# boot.net
KiCad netlist of a schematic drawn in Altium Designer
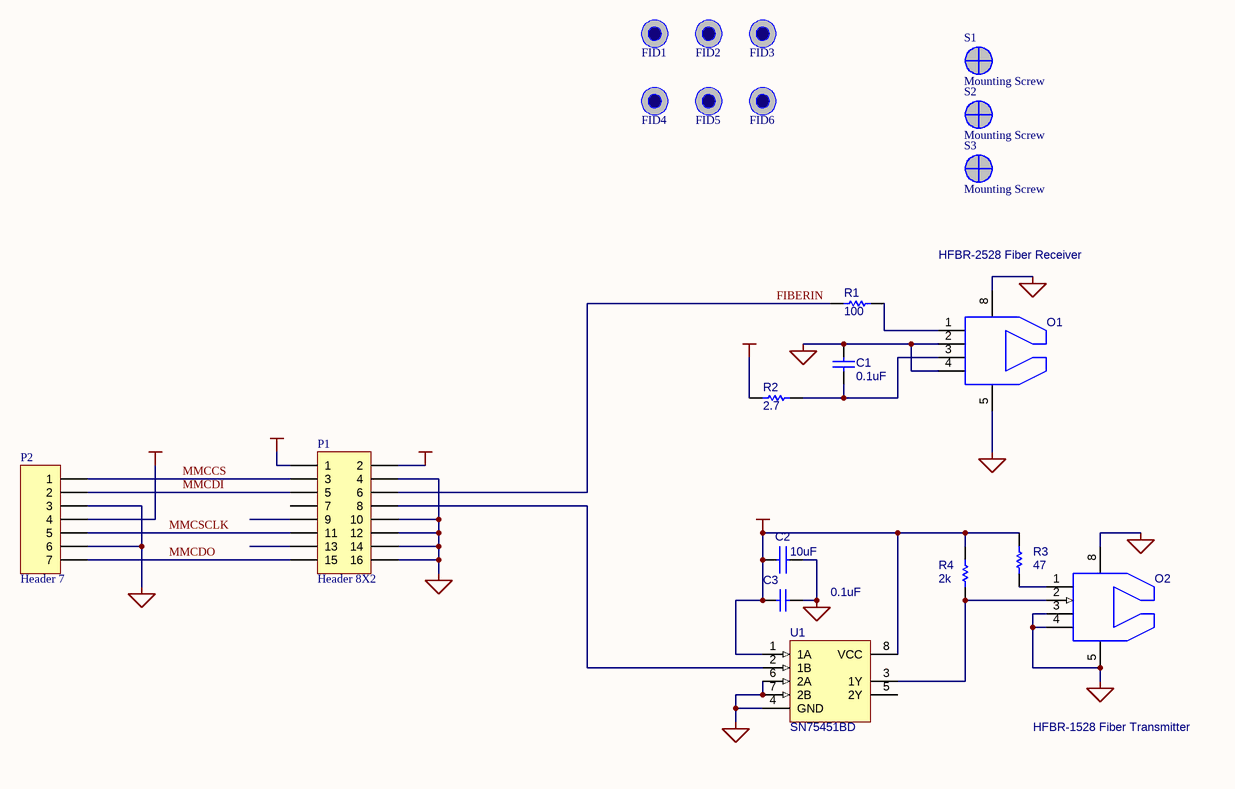
[diagram p0: boot.SCHDOC]

(export (version "E")
  (design (tool "Eeschema 10.0.6"))
  (components
    (comp (ref "C1")
      (value "0.1uF")
      (footprint "CC1608-0603")
      (description "Capacitor")
      (fields
        (field (name "MANUFACTURER") "Generic Components")
        (field (name "Comment") "Cap")
        (field (name "PUBLISHER") "Altium Limited")
      )
      (libsource (lib "Miscellaneous Devices") (part "Cap"))
    )
    (comp (ref "C2")
      (value "10uF")
      (footprint "0603")
      (description "Standard Capacitor")
      (fields (field (name "Comment") "CAPACITOR"))
      (libsource (lib "parts") (part "CAPACITOR"))
    )
    (comp (ref "C3")
      (value "0.1uF")
      (footprint "CC1608-0603")
      (description "Capacitor")
      (fields
        (field (name "MANUFACTURER") "Generic Components")
        (field (name "Comment") "Cap")
        (field (name "PUBLISHER") "Altium Limited")
      )
      (libsource (lib "Miscellaneous Devices") (part "Cap"))
    )
    (comp (ref "FID1")
      (value "FIDUCIAL")
      (footprint "FIDUCIAL")
      (description "Fiducial")
      (libsource (lib "parts") (part "FIDUCIAL"))
    )
    (comp (ref "FID2")
      (value "FIDUCIAL")
      (footprint "FIDUCIAL")
      (description "Fiducial")
      (libsource (lib "parts") (part "FIDUCIAL"))
    )
    (comp (ref "FID3")
      (value "FIDUCIAL")
      (footprint "FIDUCIAL")
      (description "Fiducial")
      (libsource (lib "parts") (part "FIDUCIAL"))
    )
    (comp (ref "FID4")
      (value "FIDUCIAL")
      (footprint "FIDUCIAL")
      (description "Fiducial")
      (libsource (lib "parts") (part "FIDUCIAL"))
    )
    (comp (ref "FID5")
      (value "FIDUCIAL")
      (footprint "FIDUCIAL")
      (description "Fiducial")
      (libsource (lib "parts") (part "FIDUCIAL"))
    )
    (comp (ref "FID6")
      (value "FIDUCIAL")
      (footprint "FIDUCIAL")
      (description "Fiducial")
      (libsource (lib "parts") (part "FIDUCIAL"))
    )
    (comp (ref "O1")
      (value "HFBR-2528 Fiber Receiver")
      (footprint "HPVL")
      (description "Low-cost fiber receiver")
      (libsource (lib "parts") (part "HFBR-2528"))
    )
    (comp (ref "O2")
      (value "HFBR-1528 Fiber Transmitter")
      (footprint "HPVL")
      (description "Low-cost fiber transmitter")
      (libsource (lib "parts") (part "HFBR-1528"))
    )
    (comp (ref "P1")
      (value "Header 8X2")
      (footprint "MOLEX 15-91-2160")
      (description "Header, 8-Pin, Dual row")
      (fields (field (name "PUBLISHER") "Altium Limited"))
      (libsource (lib "Miscellaneous Connectors") (part "Header 8X2"))
    )
    (comp (ref "P2")
      (value "Header 7")
      (footprint "SCDA1A1501")
      (description "Header, 7-Pin")
      (fields (field (name "PUBLISHER") "Altium Limited"))
      (libsource (lib "Miscellaneous Connectors") (part "Header 7"))
    )
    (comp (ref "R1")
      (value "100")
      (footprint "CR1608-0603")
      (description "Resistor")
      (fields
        (field (name "MANUFACTURER") "Generic Components")
        (field (name "Comment") "Res1")
        (field (name "PUBLISHER") "Altium Limited")
      )
      (libsource (lib "Miscellaneous Devices") (part "Res1"))
    )
    (comp (ref "R2")
      (value "2.7")
      (footprint "CR1608-0603")
      (description "Resistor")
      (fields
        (field (name "MANUFACTURER") "Generic Components")
        (field (name "Comment") "Res1")
        (field (name "PUBLISHER") "Altium Limited")
      )
      (libsource (lib "Miscellaneous Devices") (part "Res1"))
    )
    (comp (ref "R3")
      (value "47")
      (footprint "CR1608-0603")
      (description "Resistor")
      (fields
        (field (name "MANUFACTURER") "Generic Components")
        (field (name "Comment") "Res1")
        (field (name "PUBLISHER") "Altium Limited")
      )
      (libsource (lib "Miscellaneous Devices") (part "Res1"))
    )
    (comp (ref "R4")
      (value "2k")
      (footprint "CR1608-0603")
      (description "Resistor")
      (fields
        (field (name "MANUFACTURER") "Generic Components")
        (field (name "Comment") "Res1")
        (field (name "PUBLISHER") "Altium Limited")
      )
      (libsource (lib "Miscellaneous Devices") (part "Res1"))
    )
    (comp (ref "S1")
      (value "Mounting Screw")
      (footprint "SCREW6-32")
      (libsource (lib "parts") (part "MNTSCREW"))
    )
    (comp (ref "S2")
      (value "Mounting Screw")
      (footprint "SCREW6-32")
      (libsource (lib "parts") (part "MNTSCREW"))
    )
    (comp (ref "S3")
      (value "Mounting Screw")
      (footprint "SCREW6-32")
      (libsource (lib "parts") (part "MNTSCREW"))
    )
    (comp (ref "U1")
      (value "SN75451BD")
      (footprint "SO-G8/E2.5")
      (description "Dual Peripheral Driver")
      (fields (field (name "MANUFACTURER") "Texas Instruments") (field (name "PUBLISHER") "Altium Limited"))
      (libsource (lib "TI Interface Peripheral Driver") (part "SN75451BD"))
    )
  )
  (nets
    (net (code "1") (name "+5VCC") (class "Default")
      (node (ref "C2") (pin "1") (pintype "passive"))
      (node (ref "C3") (pin "1") (pinfunction "1_1") (pintype "passive"))
      (node (ref "P1") (pin "2") (pinfunction "2_2") (pintype "passive"))
      (node (ref "R2") (pin "1") (pinfunction "1_1") (pintype "passive"))
      (node (ref "R3") (pin "2") (pinfunction "2_2") (pintype "passive"))
      (node (ref "R4") (pin "2") (pinfunction "2_2") (pintype "passive"))
      (node (ref "U1") (pin "1") (pinfunction "1A_1") (pintype "input"))
      (node (ref "U1") (pin "8") (pinfunction "VCC_8") (pintype "power_in"))
    )
    (net (code "2") (name "/FIBERIN") (class "Default")
      (node (ref "P1") (pin "6") (pinfunction "6_6") (pintype "passive"))
      (node (ref "R1") (pin "1") (pinfunction "1_1") (pintype "passive"))
    )
    (net (code "3") (name "/MMCCS") (class "Default")
      (node (ref "P1") (pin "3") (pinfunction "3_3") (pintype "passive"))
      (node (ref "P2") (pin "1") (pinfunction "1_1") (pintype "passive"))
    )
    (net (code "4") (name "/MMCDI") (class "Default")
      (node (ref "P1") (pin "5") (pinfunction "5_5") (pintype "passive"))
      (node (ref "P2") (pin "2") (pinfunction "2_2") (pintype "passive"))
    )
    (net (code "5") (name "/MMCDO") (class "Default")
      (node (ref "P1") (pin "15") (pinfunction "15_15") (pintype "passive"))
      (node (ref "P2") (pin "7") (pinfunction "7_7") (pintype "passive"))
    )
    (net (code "6") (name "/MMCSCLK") (class "Default")
      (node (ref "P1") (pin "11") (pinfunction "11_11") (pintype "passive"))
      (node (ref "P2") (pin "5") (pinfunction "5_5") (pintype "passive"))
    )
    (net (code "7") (name "GND") (class "Default")
      (node (ref "C1") (pin "2") (pinfunction "2_2") (pintype "passive"))
      (node (ref "C2") (pin "2") (pintype "passive"))
      (node (ref "C3") (pin "2") (pinfunction "2_2") (pintype "passive"))
      (node (ref "O1") (pin "2") (pintype "power_in"))
      (node (ref "O1") (pin "4") (pintype "power_in"))
      (node (ref "O1") (pin "5") (pintype "power_in"))
      (node (ref "O1") (pin "8") (pintype "power_in"))
      (node (ref "O2") (pin "3") (pintype "power_in"))
      (node (ref "O2") (pin "4") (pintype "power_in"))
      (node (ref "O2") (pin "5") (pintype "power_in"))
      (node (ref "O2") (pin "8") (pintype "power_in"))
      (node (ref "P1") (pin "10") (pinfunction "10_10") (pintype "passive"))
      (node (ref "P1") (pin "12") (pinfunction "12_12") (pintype "passive"))
      (node (ref "P1") (pin "14") (pinfunction "14_14") (pintype "passive"))
      (node (ref "P1") (pin "16") (pinfunction "16_16") (pintype "passive"))
      (node (ref "P1") (pin "4") (pinfunction "4_4") (pintype "passive"))
      (node (ref "P2") (pin "3") (pinfunction "3_3") (pintype "passive"))
      (node (ref "P2") (pin "6") (pinfunction "6_6") (pintype "passive"))
      (node (ref "U1") (pin "4") (pinfunction "GND_4") (pintype "power_in"))
      (node (ref "U1") (pin "6") (pinfunction "2A_6") (pintype "input"))
      (node (ref "U1") (pin "7") (pinfunction "2B_7") (pintype "input"))
    )
    (net (code "8") (name "Net-(C1-Pad1)") (class "Default")
      (node (ref "C1") (pin "1") (pinfunction "1_1") (pintype "passive"))
      (node (ref "O1") (pin "3") (pintype "power_in"))
      (node (ref "R2") (pin "2") (pinfunction "2_2") (pintype "passive"))
    )
    (net (code "9") (name "Net-(O1-Pad1)") (class "Default")
      (node (ref "O1") (pin "1") (pintype "power_in"))
      (node (ref "R1") (pin "2") (pinfunction "2_2") (pintype "passive"))
    )
    (net (code "10") (name "Net-(O2-Pad1)") (class "Default")
      (node (ref "O2") (pin "1") (pintype "power_in"))
      (node (ref "R3") (pin "1") (pinfunction "1_1") (pintype "passive"))
    )
    (net (code "11") (name "Net-(U1-1B)") (class "Default")
      (node (ref "P1") (pin "8") (pinfunction "8_8") (pintype "passive"))
      (node (ref "U1") (pin "2") (pinfunction "1B_2") (pintype "input"))
    )
    (net (code "12") (name "Net-(U1-1Y)") (class "Default")
      (node (ref "O2") (pin "2") (pintype "input"))
      (node (ref "R4") (pin "1") (pinfunction "1_1") (pintype "passive"))
      (node (ref "U1") (pin "3") (pinfunction "1Y_3") (pintype "open_collector"))
    )
    (net (code "13") (name "VCC") (class "Default")
      (node (ref "P1") (pin "1") (pinfunction "1_1") (pintype "passive"))
      (node (ref "P2") (pin "4") (pinfunction "4_4") (pintype "passive"))
    )
    (net (code "14") (name "unconnected-(P1-Pad7)") (class "Default")
      (node (ref "P1") (pin "7") (pinfunction "7_7") (pintype "passive"))
    )
    (net (code "15") (name "unconnected-(P1-Pad9)") (class "Default")
      (node (ref "P1") (pin "9") (pinfunction "9_9") (pintype "passive"))
    )
    (net (code "16") (name "unconnected-(P1-Pad13)") (class "Default")
      (node (ref "P1") (pin "13") (pinfunction "13_13") (pintype "passive"))
    )
    (net (code "17") (name "unconnected-(U1-2Y-Pad5)") (class "Default")
      (node (ref "U1") (pin "5") (pinfunction "2Y_5") (pintype "open_collector"))
    )
  )
)
